# processing.net
KiCad netlist of a schematic drawn in EAGLE
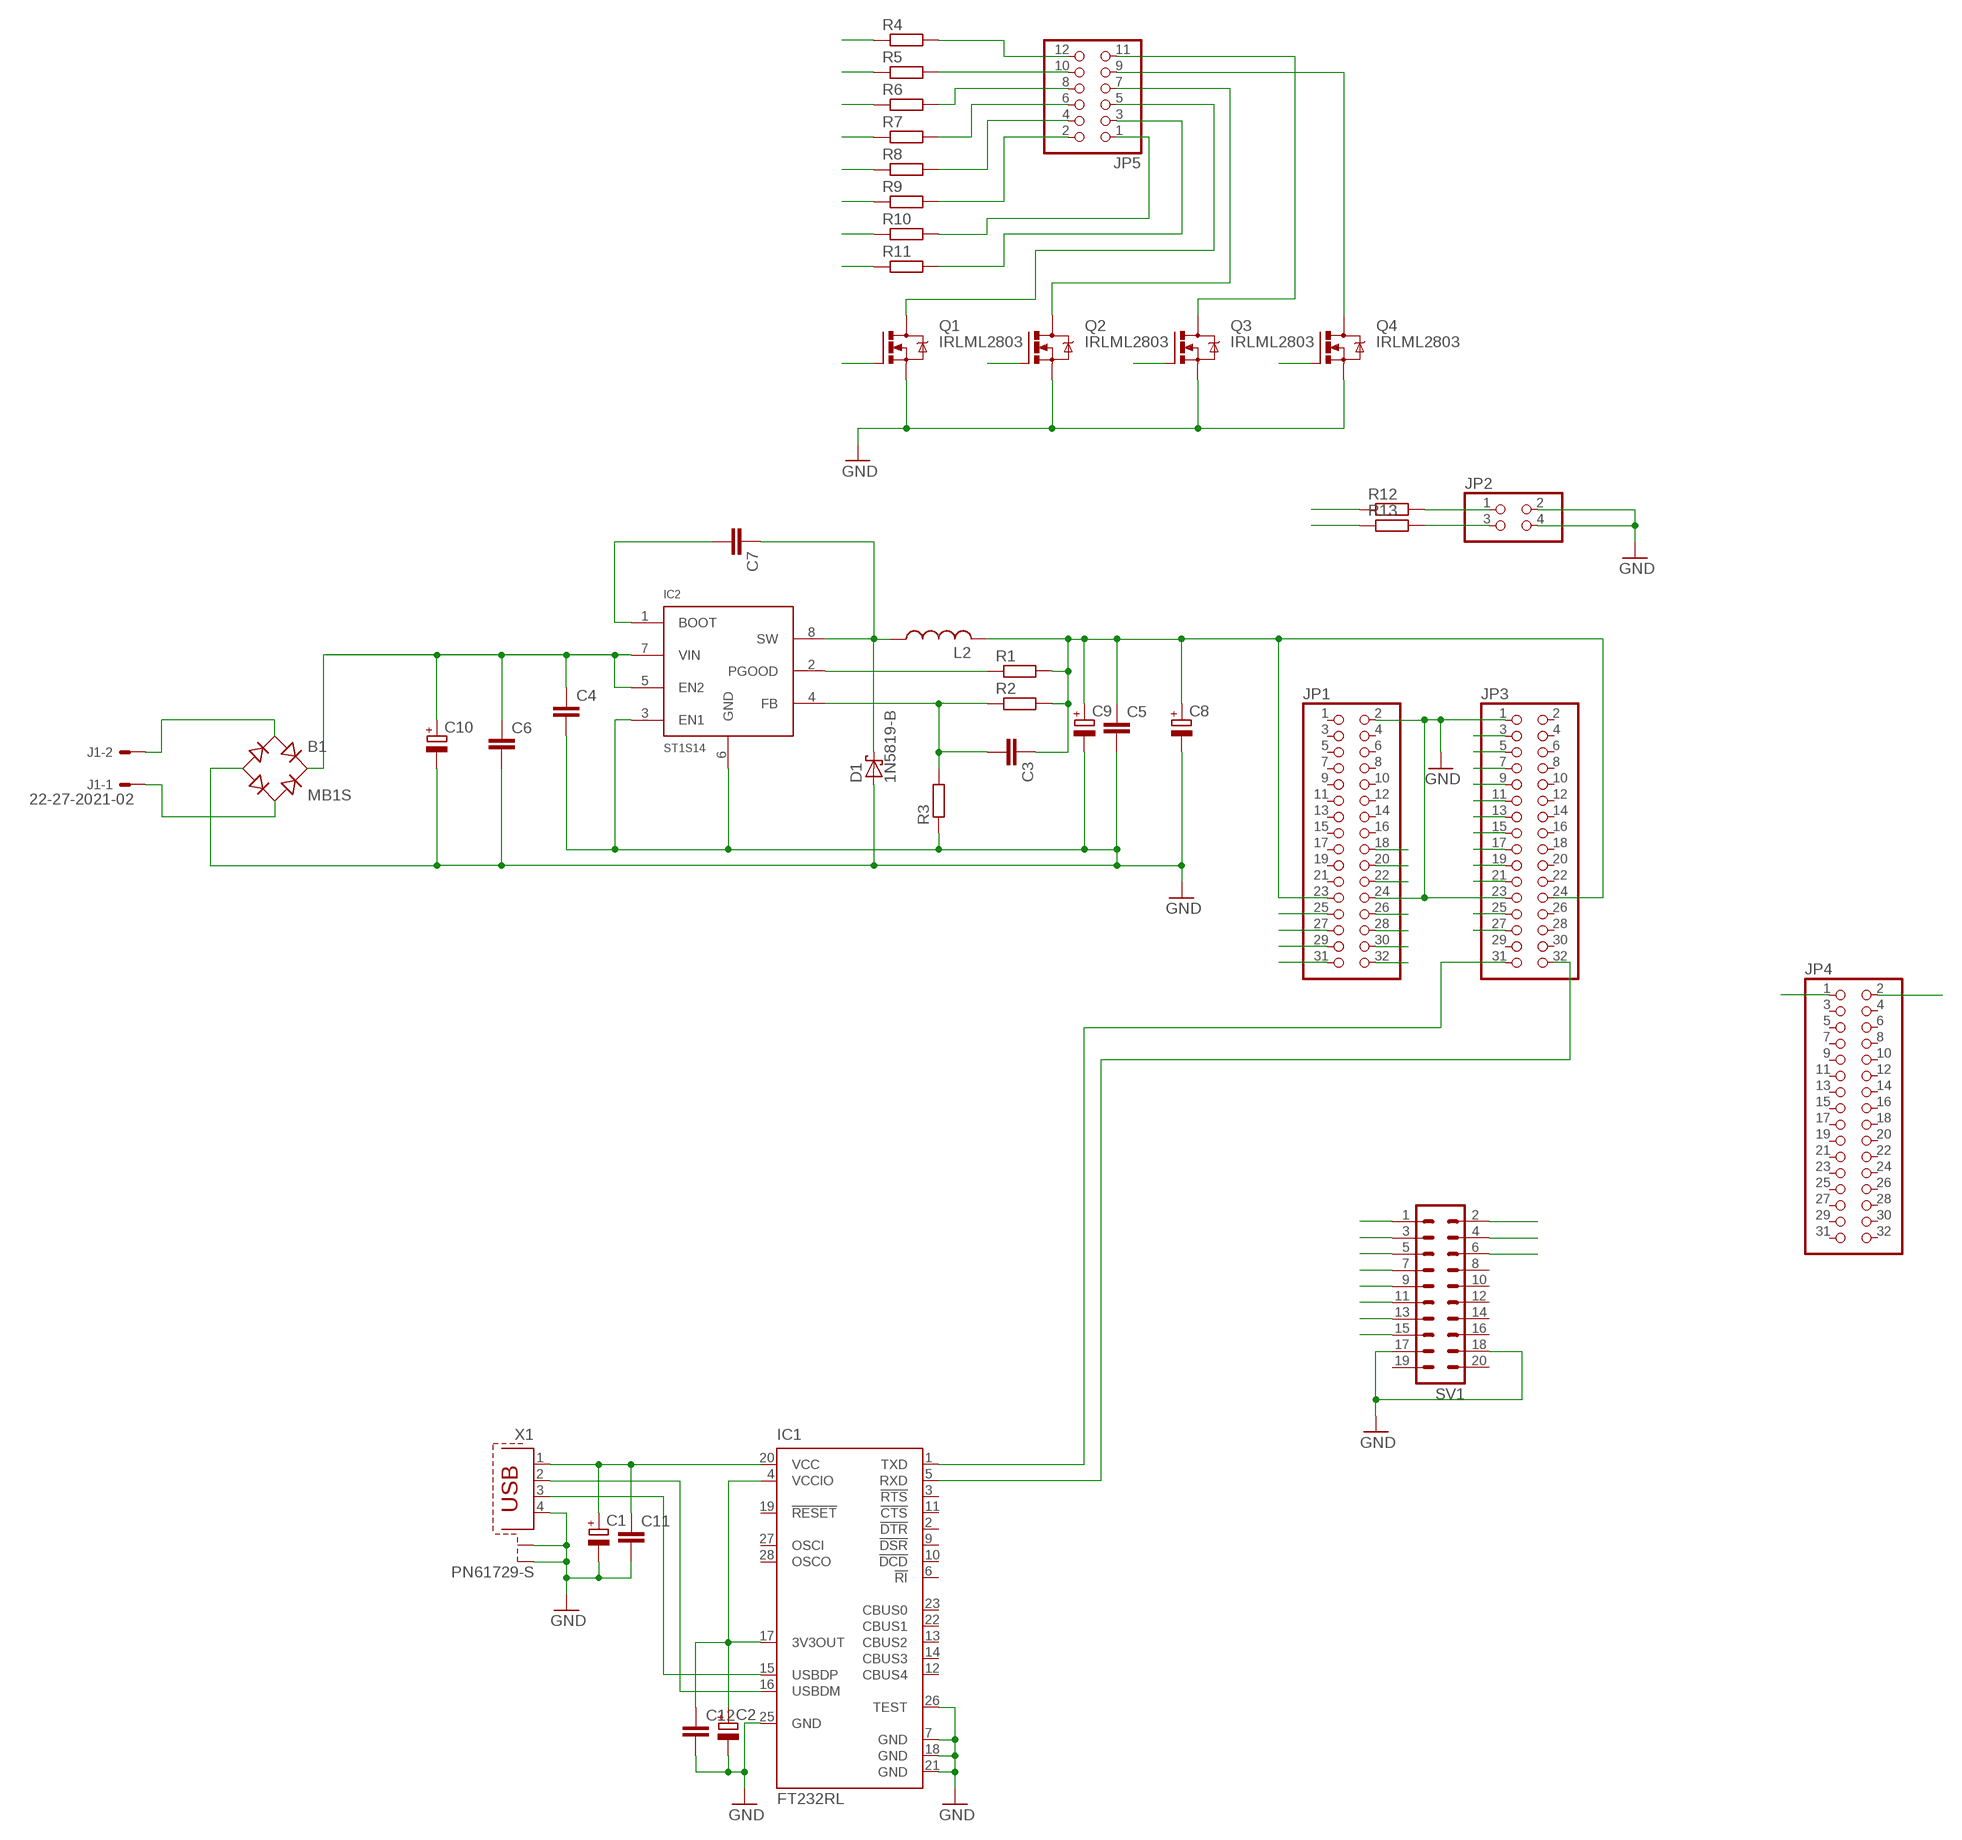
[diagram p0: schematic, sheet 1]

(export (version "E")
  (design (tool "Eeschema 10.0.6"))
  (components
    (comp (ref "B1")
      (value "MB1S")
      (footprint "eagle-import:SOIC-4")
      (libsource (lib "eagle-import") (part "MBS1"))
    )
    (comp (ref "C1")
      (value "CPOL-EUE2.5-5")
      (footprint "eagle-import:E2,5-5")
      (libsource (lib "eagle-import") (part "CPOL-EUE2.5-5"))
    )
    (comp (ref "C2")
      (value "CPOL-EUE2.5-5")
      (footprint "eagle-import:E2,5-5")
      (libsource (lib "eagle-import") (part "CPOL-EUE2.5-5"))
    )
    (comp (ref "C3")
      (value "C-EUC0805")
      (footprint "eagle-import:C0805")
      (libsource (lib "eagle-import") (part "C-EUC0805"))
    )
    (comp (ref "C4")
      (value "C-EUC0805")
      (footprint "eagle-import:C0805")
      (libsource (lib "eagle-import") (part "C-EUC0805"))
    )
    (comp (ref "C5")
      (value "C-EUC0805")
      (footprint "eagle-import:C0805")
      (libsource (lib "eagle-import") (part "C-EUC0805"))
    )
    (comp (ref "C6")
      (value "C-EUC0805")
      (footprint "eagle-import:C0805")
      (libsource (lib "eagle-import") (part "C-EUC0805"))
    )
    (comp (ref "C7")
      (value "C-EUC0805")
      (footprint "eagle-import:C0805")
      (libsource (lib "eagle-import") (part "C-EUC0805"))
    )
    (comp (ref "C8")
      (value "CPOL-EUE2.5-6")
      (footprint "eagle-import:E2,5-6")
      (libsource (lib "eagle-import") (part "CPOL-EUE2.5-6"))
    )
    (comp (ref "C9")
      (value "CPOL-EUSMCB")
      (footprint "eagle-import:SMC_B")
      (libsource (lib "eagle-import") (part "CPOL-EUSMCB"))
    )
    (comp (ref "C10")
      (value "CPOL-EUE2.5-7")
      (footprint "eagle-import:E2,5-7")
      (libsource (lib "eagle-import") (part "CPOL-EUE2.5-7"))
    )
    (comp (ref "C11")
      (value "C-EUC0603")
      (footprint "eagle-import:C0603")
      (libsource (lib "eagle-import") (part "C-EUC0603"))
    )
    (comp (ref "C12")
      (value "C-EUC0603")
      (footprint "eagle-import:C0603")
      (libsource (lib "eagle-import") (part "C-EUC0603"))
    )
    (comp (ref "D1")
      (value "1N5819-B")
      (footprint "eagle-import:DO41-7.6")
      (libsource (lib "eagle-import") (part "1N5819-B"))
    )
    (comp (ref "IC1")
      (value "FT232RL")
      (footprint "eagle-import:SSOP28")
      (libsource (lib "eagle-import") (part "FT232RL"))
    )
    (comp (ref "IC2")
      (value "ST1S14")
      (footprint "eagle-import:SO8")
      (libsource (lib "eagle-import") (part "ST1S14"))
    )
    (comp (ref "J1")
      (value "22-27-2021-02")
      (footprint "eagle-import:6410-02")
      (libsource (lib "eagle-import") (part "22-?-0227-2021"))
    )
    (comp (ref "JP1")
      (value "PINHD-2X16M")
      (footprint "eagle-import:2X16M")
      (libsource (lib "eagle-import") (part "PINHD-2X16M"))
    )
    (comp (ref "JP2")
      (value "PINHD-2X2")
      (footprint "eagle-import:2X02")
      (libsource (lib "eagle-import") (part "PINHD-2X2"))
    )
    (comp (ref "JP3")
      (value "PINHD-2X16M")
      (footprint "eagle-import:2X16M")
      (libsource (lib "eagle-import") (part "PINHD-2X16M"))
    )
    (comp (ref "JP4")
      (value "PINHD-2X16M")
      (footprint "eagle-import:2X16M")
      (libsource (lib "eagle-import") (part "PINHD-2X16M"))
    )
    (comp (ref "JP5")
      (value "PINHD-2X6")
      (footprint "eagle-import:2X06")
      (libsource (lib "eagle-import") (part "PINHD-2X6"))
    )
    (comp (ref "L2")
      (value "L-USWE-TPC")
      (footprint "eagle-import:POWER-CHOKE_WE-TPC")
      (libsource (lib "eagle-import") (part "L-USWE-TPC"))
    )
    (comp (ref "Q1")
      (value "IRLML2803")
      (footprint "eagle-import:SOT23")
      (libsource (lib "eagle-import") (part "IRLML2803"))
    )
    (comp (ref "Q2")
      (value "IRLML2803")
      (footprint "eagle-import:SOT23")
      (libsource (lib "eagle-import") (part "IRLML2803"))
    )
    (comp (ref "Q3")
      (value "IRLML2803")
      (footprint "eagle-import:SOT23")
      (libsource (lib "eagle-import") (part "IRLML2803"))
    )
    (comp (ref "Q4")
      (value "IRLML2803")
      (footprint "eagle-import:SOT23")
      (libsource (lib "eagle-import") (part "IRLML2803"))
    )
    (comp (ref "R1")
      (value "R-EU_R0805")
      (footprint "eagle-import:R0805")
      (libsource (lib "eagle-import") (part "R-EU_R0805"))
    )
    (comp (ref "R2")
      (value "R-EU_R0805")
      (footprint "eagle-import:R0805")
      (libsource (lib "eagle-import") (part "R-EU_R0805"))
    )
    (comp (ref "R3")
      (value "R-EU_R0805")
      (footprint "eagle-import:R0805")
      (libsource (lib "eagle-import") (part "R-EU_R0805"))
    )
    (comp (ref "R4")
      (value "R-EU_R0603")
      (footprint "eagle-import:R0603")
      (libsource (lib "eagle-import") (part "R-EU_R0603"))
    )
    (comp (ref "R5")
      (value "R-EU_R0603")
      (footprint "eagle-import:R0603")
      (libsource (lib "eagle-import") (part "R-EU_R0603"))
    )
    (comp (ref "R6")
      (value "R-EU_R0603")
      (footprint "eagle-import:R0603")
      (libsource (lib "eagle-import") (part "R-EU_R0603"))
    )
    (comp (ref "R7")
      (value "R-EU_R0603")
      (footprint "eagle-import:R0603")
      (libsource (lib "eagle-import") (part "R-EU_R0603"))
    )
    (comp (ref "R8")
      (value "R-EU_R0603")
      (footprint "eagle-import:R0603")
      (libsource (lib "eagle-import") (part "R-EU_R0603"))
    )
    (comp (ref "R9")
      (value "R-EU_R0603")
      (footprint "eagle-import:R0603")
      (libsource (lib "eagle-import") (part "R-EU_R0603"))
    )
    (comp (ref "R10")
      (value "R-EU_R0603")
      (footprint "eagle-import:R0603")
      (libsource (lib "eagle-import") (part "R-EU_R0603"))
    )
    (comp (ref "R11")
      (value "R-EU_R0603")
      (footprint "eagle-import:R0603")
      (libsource (lib "eagle-import") (part "R-EU_R0603"))
    )
    (comp (ref "R12")
      (value "R-EU_R0603")
      (footprint "eagle-import:R0603")
      (libsource (lib "eagle-import") (part "R-EU_R0603"))
    )
    (comp (ref "R13")
      (value "R-EU_R0603")
      (footprint "eagle-import:R0603")
      (libsource (lib "eagle-import") (part "R-EU_R0603"))
    )
    (comp (ref "SV1")
      (value "MA10-2W")
      (footprint "eagle-import:MA10-2W")
      (libsource (lib "eagle-import") (part "MA10-2W"))
    )
    (comp (ref "X1")
      (value "PN61729-S")
      (footprint "eagle-import:PN61729-S")
      (libsource (lib "eagle-import") (part "PN61729-S"))
    )
  )
  (nets
    (net (code "1") (name "/L1") (class "Default")
      (node (ref "JP3") (pin "17") (pinfunction "17_17") (pintype "passive"))
      (node (ref "R4") (pin "1") (pinfunction "1_1") (pintype "passive"))
    )
    (net (code "2") (name "/L2") (class "Default")
      (node (ref "JP3") (pin "15") (pinfunction "15_15") (pintype "passive"))
      (node (ref "R5") (pin "1") (pinfunction "1_1") (pintype "passive"))
    )
    (net (code "3") (name "/L3") (class "Default")
      (node (ref "JP3") (pin "13") (pinfunction "13_13") (pintype "passive"))
      (node (ref "R6") (pin "1") (pinfunction "1_1") (pintype "passive"))
    )
    (net (code "4") (name "/L4") (class "Default")
      (node (ref "JP3") (pin "11") (pinfunction "11_11") (pintype "passive"))
      (node (ref "R7") (pin "1") (pinfunction "1_1") (pintype "passive"))
    )
    (net (code "5") (name "/L5") (class "Default")
      (node (ref "JP3") (pin "9") (pinfunction "9_9") (pintype "passive"))
      (node (ref "R8") (pin "1") (pinfunction "1_1") (pintype "passive"))
    )
    (net (code "6") (name "/L6") (class "Default")
      (node (ref "JP3") (pin "7") (pinfunction "7_7") (pintype "passive"))
      (node (ref "R9") (pin "1") (pinfunction "1_1") (pintype "passive"))
    )
    (net (code "7") (name "/L7") (class "Default")
      (node (ref "JP3") (pin "5") (pinfunction "5_5") (pintype "passive"))
      (node (ref "R10") (pin "1") (pinfunction "1_1") (pintype "passive"))
    )
    (net (code "8") (name "/L8") (class "Default")
      (node (ref "JP3") (pin "3") (pinfunction "3_3") (pintype "passive"))
      (node (ref "R11") (pin "1") (pinfunction "1_1") (pintype "passive"))
    )
    (net (code "9") (name "/LED1") (class "Default")
      (node (ref "JP4") (pin "1") (pinfunction "1_1") (pintype "passive"))
      (node (ref "R12") (pin "1") (pinfunction "1_1") (pintype "passive"))
    )
    (net (code "10") (name "/LED2") (class "Default")
      (node (ref "JP4") (pin "2") (pinfunction "2_2") (pintype "passive"))
      (node (ref "R13") (pin "1") (pinfunction "1_1") (pintype "passive"))
    )
    (net (code "11") (name "/Q1") (class "Default")
      (node (ref "JP3") (pin "27") (pinfunction "27_27") (pintype "passive"))
      (node (ref "Q1") (pin "1") (pinfunction "G_1") (pintype "passive"))
    )
    (net (code "12") (name "/Q2") (class "Default")
      (node (ref "JP3") (pin "25") (pinfunction "25_25") (pintype "passive"))
      (node (ref "Q2") (pin "1") (pinfunction "G_1") (pintype "passive"))
    )
    (net (code "13") (name "/Q3") (class "Default")
      (node (ref "JP3") (pin "19") (pinfunction "19_19") (pintype "passive"))
      (node (ref "Q3") (pin "1") (pinfunction "G_1") (pintype "passive"))
    )
    (net (code "14") (name "/Q4") (class "Default")
      (node (ref "JP3") (pin "21") (pinfunction "21_21") (pintype "passive"))
      (node (ref "Q4") (pin "1") (pinfunction "G_1") (pintype "passive"))
    )
    (net (code "15") (name "/R1") (class "Default")
      (node (ref "JP1") (pin "18") (pinfunction "18_18") (pintype "passive"))
      (node (ref "SV1") (pin "6") (pinfunction "6_6") (pintype "passive"))
    )
    (net (code "16") (name "/R2") (class "Default")
      (node (ref "JP1") (pin "20") (pinfunction "20_20") (pintype "passive"))
      (node (ref "SV1") (pin "4") (pinfunction "4_4") (pintype "passive"))
    )
    (net (code "17") (name "/R3") (class "Default")
      (node (ref "JP1") (pin "22") (pinfunction "22_22") (pintype "passive"))
      (node (ref "SV1") (pin "2") (pinfunction "2_2") (pintype "passive"))
    )
    (net (code "18") (name "/R4") (class "Default")
      (node (ref "JP1") (pin "26") (pinfunction "26_26") (pintype "passive"))
      (node (ref "SV1") (pin "1") (pinfunction "1_1") (pintype "passive"))
    )
    (net (code "19") (name "/R5") (class "Default")
      (node (ref "JP1") (pin "28") (pinfunction "28_28") (pintype "passive"))
      (node (ref "SV1") (pin "3") (pinfunction "3_3") (pintype "passive"))
    )
    (net (code "20") (name "/R6") (class "Default")
      (node (ref "JP1") (pin "30") (pinfunction "30_30") (pintype "passive"))
      (node (ref "SV1") (pin "5") (pinfunction "5_5") (pintype "passive"))
    )
    (net (code "21") (name "/R7") (class "Default")
      (node (ref "JP1") (pin "32") (pinfunction "32_32") (pintype "passive"))
      (node (ref "SV1") (pin "7") (pinfunction "7_7") (pintype "passive"))
    )
    (net (code "22") (name "/R8") (class "Default")
      (node (ref "JP1") (pin "31") (pinfunction "31_31") (pintype "passive"))
      (node (ref "SV1") (pin "9") (pinfunction "9_9") (pintype "passive"))
    )
    (net (code "23") (name "/R9") (class "Default")
      (node (ref "JP1") (pin "29") (pinfunction "29_29") (pintype "passive"))
      (node (ref "SV1") (pin "11") (pinfunction "11_11") (pintype "passive"))
    )
    (net (code "24") (name "/R10") (class "Default")
      (node (ref "JP1") (pin "27") (pinfunction "27_27") (pintype "passive"))
      (node (ref "SV1") (pin "13") (pinfunction "13_13") (pintype "passive"))
    )
    (net (code "25") (name "/R11") (class "Default")
      (node (ref "JP1") (pin "25") (pinfunction "25_25") (pintype "passive"))
      (node (ref "SV1") (pin "15") (pinfunction "15_15") (pintype "passive"))
    )
    (net (code "26") (name "GND") (class "Default")
      (node (ref "B1") (pin "-") (pinfunction "-_-") (pintype "passive"))
      (node (ref "C1") (pin "-") (pinfunction "-_-") (pintype "passive"))
      (node (ref "C10") (pin "-") (pinfunction "-_-") (pintype "passive"))
      (node (ref "C11") (pin "2") (pinfunction "2_2") (pintype "passive"))
      (node (ref "C12") (pin "2") (pinfunction "2_2") (pintype "passive"))
      (node (ref "C2") (pin "-") (pinfunction "-_-") (pintype "passive"))
      (node (ref "C4") (pin "2") (pinfunction "2_2") (pintype "passive"))
      (node (ref "C5") (pin "2") (pinfunction "2_2") (pintype "passive"))
      (node (ref "C6") (pin "2") (pinfunction "2_2") (pintype "passive"))
      (node (ref "C8") (pin "-") (pinfunction "-_-") (pintype "passive"))
      (node (ref "C9") (pin "-") (pinfunction "-_-") (pintype "passive"))
      (node (ref "D1") (pin "A") (pinfunction "A_A") (pintype "passive"))
      (node (ref "IC1") (pin "18") (pinfunction "GND_18") (pintype "power_in"))
      (node (ref "IC1") (pin "21") (pinfunction "GND_21") (pintype "power_in"))
      (node (ref "IC1") (pin "25") (pinfunction "GND_25") (pintype "power_in"))
      (node (ref "IC1") (pin "26") (pinfunction "TEST_26") (pintype "input"))
      (node (ref "IC1") (pin "7") (pinfunction "GND_7") (pintype "power_in"))
      (node (ref "IC2") (pin "3") (pinfunction "EN1_3") (pintype "bidirectional"))
      (node (ref "IC2") (pin "6") (pinfunction "GND_6") (pintype "bidirectional"))
      (node (ref "JP1") (pin "2") (pinfunction "2_2") (pintype "passive"))
      (node (ref "JP1") (pin "24") (pinfunction "24_24") (pintype "passive"))
      (node (ref "JP2") (pin "2") (pinfunction "2_2") (pintype "passive"))
      (node (ref "JP2") (pin "4") (pinfunction "4_4") (pintype "passive"))
      (node (ref "JP3") (pin "1") (pinfunction "1_1") (pintype "passive"))
      (node (ref "JP3") (pin "23") (pinfunction "23_23") (pintype "passive"))
      (node (ref "Q1") (pin "2") (pinfunction "S_2") (pintype "passive"))
      (node (ref "Q2") (pin "2") (pinfunction "S_2") (pintype "passive"))
      (node (ref "Q3") (pin "2") (pinfunction "S_2") (pintype "passive"))
      (node (ref "Q4") (pin "2") (pinfunction "S_2") (pintype "passive"))
      (node (ref "R3") (pin "1") (pinfunction "1_1") (pintype "passive"))
      (node (ref "SV1") (pin "17") (pinfunction "17_17") (pintype "passive"))
      (node (ref "SV1") (pin "18") (pinfunction "18_18") (pintype "passive"))
      (node (ref "X1") (pin "4") (pinfunction "4_4") (pintype "passive"))
      (node (ref "X1") (pin "S1") (pinfunction "S1_S1") (pintype "passive"))
      (node (ref "X1") (pin "S2") (pinfunction "S2_S2") (pintype "passive"))
    )
    (net (code "27") (name "Net-(B1-AC1)") (class "Default")
      (node (ref "B1") (pin "~1") (pinfunction "AC1_~1") (pintype "passive"))
      (node (ref "J1") (pin "2") (pinfunction "S_2") (pintype "passive"))
    )
    (net (code "28") (name "Net-(B1-AC2)") (class "Default")
      (node (ref "B1") (pin "~2") (pinfunction "AC2_~2") (pintype "passive"))
      (node (ref "J1") (pin "1") (pinfunction "S_1") (pintype "passive"))
    )
    (net (code "29") (name "Net-(C3-Pad1)") (class "Default")
      (node (ref "C3") (pin "1") (pinfunction "1_1") (pintype "passive"))
      (node (ref "C5") (pin "1") (pinfunction "1_1") (pintype "passive"))
      (node (ref "C8") (pin "+") (pinfunction "+_+") (pintype "passive"))
      (node (ref "C9") (pin "+") (pinfunction "+_+") (pintype "passive"))
      (node (ref "JP1") (pin "23") (pinfunction "23_23") (pintype "passive"))
      (node (ref "JP3") (pin "24") (pinfunction "24_24") (pintype "passive"))
      (node (ref "L2") (pin "2") (pinfunction "2_2") (pintype "passive"))
      (node (ref "R1") (pin "2") (pinfunction "2_2") (pintype "passive"))
      (node (ref "R2") (pin "2") (pinfunction "2_2") (pintype "passive"))
    )
    (net (code "30") (name "Net-(IC1-3V3OUT)") (class "Default")
      (node (ref "C12") (pin "1") (pinfunction "1_1") (pintype "passive"))
      (node (ref "C2") (pin "+") (pinfunction "+_+") (pintype "passive"))
      (node (ref "IC1") (pin "17") (pinfunction "3V3OUT_17") (pintype "output"))
      (node (ref "IC1") (pin "4") (pinfunction "VCCIO_4") (pintype "power_in"))
    )
    (net (code "31") (name "Net-(IC1-RXD)") (class "Default")
      (node (ref "IC1") (pin "5") (pinfunction "RXD_5") (pintype "input"))
      (node (ref "JP3") (pin "32") (pinfunction "32_32") (pintype "passive"))
    )
    (net (code "32") (name "Net-(IC1-TXD)") (class "Default")
      (node (ref "IC1") (pin "1") (pinfunction "TXD_1") (pintype "output"))
      (node (ref "JP3") (pin "31") (pinfunction "31_31") (pintype "passive"))
    )
    (net (code "33") (name "Net-(IC1-USBDM)") (class "Default")
      (node (ref "IC1") (pin "16") (pinfunction "USBDM_16") (pintype "bidirectional"))
      (node (ref "X1") (pin "2") (pinfunction "2_2") (pintype "passive"))
    )
    (net (code "34") (name "Net-(IC1-USBDP)") (class "Default")
      (node (ref "IC1") (pin "15") (pinfunction "USBDP_15") (pintype "bidirectional"))
      (node (ref "X1") (pin "3") (pinfunction "3_3") (pintype "passive"))
    )
    (net (code "35") (name "Net-(IC1-VCC)") (class "Default")
      (node (ref "C1") (pin "+") (pinfunction "+_+") (pintype "passive"))
      (node (ref "C11") (pin "1") (pinfunction "1_1") (pintype "passive"))
      (node (ref "IC1") (pin "20") (pinfunction "VCC_20") (pintype "power_in"))
      (node (ref "X1") (pin "1") (pinfunction "1_1") (pintype "passive"))
    )
    (net (code "36") (name "Net-(IC2-BOOT)") (class "Default")
      (node (ref "C7") (pin "2") (pinfunction "2_2") (pintype "passive"))
      (node (ref "IC2") (pin "1") (pinfunction "BOOT_1") (pintype "bidirectional"))
    )
    (net (code "37") (name "Net-(IC2-EN2)") (class "Default")
      (node (ref "B1") (pin "+") (pinfunction "+_+") (pintype "passive"))
      (node (ref "C10") (pin "+") (pinfunction "+_+") (pintype "passive"))
      (node (ref "C4") (pin "1") (pinfunction "1_1") (pintype "passive"))
      (node (ref "C6") (pin "1") (pinfunction "1_1") (pintype "passive"))
      (node (ref "IC2") (pin "5") (pinfunction "EN2_5") (pintype "bidirectional"))
      (node (ref "IC2") (pin "7") (pinfunction "VIN_7") (pintype "bidirectional"))
    )
    (net (code "38") (name "Net-(IC2-FB)") (class "Default")
      (node (ref "C3") (pin "2") (pinfunction "2_2") (pintype "passive"))
      (node (ref "IC2") (pin "4") (pinfunction "FB_4") (pintype "bidirectional"))
      (node (ref "R2") (pin "1") (pinfunction "1_1") (pintype "passive"))
      (node (ref "R3") (pin "2") (pinfunction "2_2") (pintype "passive"))
    )
    (net (code "39") (name "Net-(IC2-PGOOD)") (class "Default")
      (node (ref "IC2") (pin "2") (pinfunction "PGOOD_2") (pintype "bidirectional"))
      (node (ref "R1") (pin "1") (pinfunction "1_1") (pintype "passive"))
    )
    (net (code "40") (name "Net-(IC2-SW)") (class "Default")
      (node (ref "C7") (pin "1") (pinfunction "1_1") (pintype "passive"))
      (node (ref "D1") (pin "C") (pinfunction "C_C") (pintype "passive"))
      (node (ref "IC2") (pin "8") (pinfunction "SW_8") (pintype "bidirectional"))
      (node (ref "L2") (pin "1") (pinfunction "1_1") (pintype "passive"))
    )
    (net (code "41") (name "Net-(JP2-Pad1)") (class "Default")
      (node (ref "JP2") (pin "1") (pinfunction "1_1") (pintype "passive"))
      (node (ref "R12") (pin "2") (pinfunction "2_2") (pintype "passive"))
    )
    (net (code "42") (name "Net-(JP2-Pad3)") (class "Default")
      (node (ref "JP2") (pin "3") (pinfunction "3_3") (pintype "passive"))
      (node (ref "R13") (pin "2") (pinfunction "2_2") (pintype "passive"))
    )
    (net (code "43") (name "Net-(JP5-Pad1)") (class "Default")
      (node (ref "JP5") (pin "1") (pinfunction "1_1") (pintype "passive"))
      (node (ref "R10") (pin "2") (pinfunction "2_2") (pintype "passive"))
    )
    (net (code "44") (name "Net-(JP5-Pad2)") (class "Default")
      (node (ref "JP5") (pin "2") (pinfunction "2_2") (pintype "passive"))
      (node (ref "R9") (pin "2") (pinfunction "2_2") (pintype "passive"))
    )
    (net (code "45") (name "Net-(JP5-Pad3)") (class "Default")
      (node (ref "JP5") (pin "3") (pinfunction "3_3") (pintype "passive"))
      (node (ref "R11") (pin "2") (pinfunction "2_2") (pintype "passive"))
    )
    (net (code "46") (name "Net-(JP5-Pad4)") (class "Default")
      (node (ref "JP5") (pin "4") (pinfunction "4_4") (pintype "passive"))
      (node (ref "R8") (pin "2") (pinfunction "2_2") (pintype "passive"))
    )
    (net (code "47") (name "Net-(JP5-Pad6)") (class "Default")
      (node (ref "JP5") (pin "6") (pinfunction "6_6") (pintype "passive"))
      (node (ref "R7") (pin "2") (pinfunction "2_2") (pintype "passive"))
    )
    (net (code "48") (name "Net-(JP5-Pad8)") (class "Default")
      (node (ref "JP5") (pin "8") (pinfunction "8_8") (pintype "passive"))
      (node (ref "R6") (pin "2") (pinfunction "2_2") (pintype "passive"))
    )
    (net (code "49") (name "Net-(JP5-Pad10)") (class "Default")
      (node (ref "JP5") (pin "10") (pinfunction "10_10") (pintype "passive"))
      (node (ref "R5") (pin "2") (pinfunction "2_2") (pintype "passive"))
    )
    (net (code "50") (name "Net-(JP5-Pad12)") (class "Default")
      (node (ref "JP5") (pin "12") (pinfunction "12_12") (pintype "passive"))
      (node (ref "R4") (pin "2") (pinfunction "2_2") (pintype "passive"))
    )
    (net (code "51") (name "Net-(Q1-D)") (class "Default")
      (node (ref "JP5") (pin "5") (pinfunction "5_5") (pintype "passive"))
      (node (ref "Q1") (pin "3") (pinfunction "D_3") (pintype "passive"))
    )
    (net (code "52") (name "Net-(Q2-D)") (class "Default")
      (node (ref "JP5") (pin "7") (pinfunction "7_7") (pintype "passive"))
      (node (ref "Q2") (pin "3") (pinfunction "D_3") (pintype "passive"))
    )
    (net (code "53") (name "Net-(Q3-D)") (class "Default")
      (node (ref "JP5") (pin "11") (pinfunction "11_11") (pintype "passive"))
      (node (ref "Q3") (pin "3") (pinfunction "D_3") (pintype "passive"))
    )
    (net (code "54") (name "Net-(Q4-D)") (class "Default")
      (node (ref "JP5") (pin "9") (pinfunction "9_9") (pintype "passive"))
      (node (ref "Q4") (pin "3") (pinfunction "D_3") (pintype "passive"))
    )
    (net (code "55") (name "unconnected-(IC1-CBUS0-Pad23)") (class "Default")
      (node (ref "IC1") (pin "23") (pinfunction "CBUS0_23") (pintype "bidirectional"))
    )
    (net (code "56") (name "unconnected-(IC1-CBUS1-Pad22)") (class "Default")
      (node (ref "IC1") (pin "22") (pinfunction "CBUS1_22") (pintype "bidirectional"))
    )
    (net (code "57") (name "unconnected-(IC1-CBUS2-Pad13)") (class "Default")
      (node (ref "IC1") (pin "13") (pinfunction "CBUS2_13") (pintype "bidirectional"))
    )
    (net (code "58") (name "unconnected-(IC1-CBUS3-Pad14)") (class "Default")
      (node (ref "IC1") (pin "14") (pinfunction "CBUS3_14") (pintype "bidirectional"))
    )
    (net (code "59") (name "unconnected-(IC1-CBUS4-Pad12)") (class "Default")
      (node (ref "IC1") (pin "12") (pinfunction "CBUS4_12") (pintype "bidirectional"))
    )
    (net (code "60") (name "unconnected-(IC1-OSCI-Pad27)") (class "Default")
      (node (ref "IC1") (pin "27") (pinfunction "OSCI_27") (pintype "input"))
    )
    (net (code "61") (name "unconnected-(IC1-OSCO-Pad28)") (class "Default")
      (node (ref "IC1") (pin "28") (pinfunction "OSCO_28") (pintype "output"))
    )
    (net (code "62") (name "unconnected-(IC1-~{CTS}-Pad11)") (class "Default")
      (node (ref "IC1") (pin "11") (pinfunction "~{CTS}_11") (pintype "input"))
    )
    (net (code "63") (name "unconnected-(IC1-~{DCD}-Pad10)") (class "Default")
      (node (ref "IC1") (pin "10") (pinfunction "~{DCD}_10") (pintype "input"))
    )
    (net (code "64") (name "unconnected-(IC1-~{DSR}-Pad9)") (class "Default")
      (node (ref "IC1") (pin "9") (pinfunction "~{DSR}_9") (pintype "input"))
    )
    (net (code "65") (name "unconnected-(IC1-~{DTR}-Pad2)") (class "Default")
      (node (ref "IC1") (pin "2") (pinfunction "~{DTR}_2") (pintype "output"))
    )
    (net (code "66") (name "unconnected-(IC1-~{RESET}-Pad19)") (class "Default")
      (node (ref "IC1") (pin "19") (pinfunction "~{RESET}_19") (pintype "input"))
    )
    (net (code "67") (name "unconnected-(IC1-~{RI}-Pad6)") (class "Default")
      (node (ref "IC1") (pin "6") (pinfunction "~{RI}_6") (pintype "input"))
    )
    (net (code "68") (name "unconnected-(IC1-~{RTS}-Pad3)") (class "Default")
      (node (ref "IC1") (pin "3") (pinfunction "~{RTS}_3") (pintype "output"))
    )
    (net (code "69") (name "unconnected-(JP1-Pad1)") (class "Default")
      (node (ref "JP1") (pin "1") (pinfunction "1_1") (pintype "passive"))
    )
    (net (code "70") (name "unconnected-(JP1-Pad3)") (class "Default")
      (node (ref "JP1") (pin "3") (pinfunction "3_3") (pintype "passive"))
    )
    (net (code "71") (name "unconnected-(JP1-Pad4)") (class "Default")
      (node (ref "JP1") (pin "4") (pinfunction "4_4") (pintype "passive"))
    )
    (net (code "72") (name "unconnected-(JP1-Pad5)") (class "Default")
      (node (ref "JP1") (pin "5") (pinfunction "5_5") (pintype "passive"))
    )
    (net (code "73") (name "unconnected-(JP1-Pad6)") (class "Default")
      (node (ref "JP1") (pin "6") (pinfunction "6_6") (pintype "passive"))
    )
    (net (code "74") (name "unconnected-(JP1-Pad7)") (class "Default")
      (node (ref "JP1") (pin "7") (pinfunction "7_7") (pintype "passive"))
    )
    (net (code "75") (name "unconnected-(JP1-Pad8)") (class "Default")
      (node (ref "JP1") (pin "8") (pinfunction "8_8") (pintype "passive"))
    )
    (net (code "76") (name "unconnected-(JP1-Pad9)") (class "Default")
      (node (ref "JP1") (pin "9") (pinfunction "9_9") (pintype "passive"))
    )
    (net (code "77") (name "unconnected-(JP1-Pad10)") (class "Default")
      (node (ref "JP1") (pin "10") (pinfunction "10_10") (pintype "passive"))
    )
    (net (code "78") (name "unconnected-(JP1-Pad11)") (class "Default")
      (node (ref "JP1") (pin "11") (pinfunction "11_11") (pintype "passive"))
    )
    (net (code "79") (name "unconnected-(JP1-Pad12)") (class "Default")
      (node (ref "JP1") (pin "12") (pinfunction "12_12") (pintype "passive"))
    )
    (net (code "80") (name "unconnected-(JP1-Pad13)") (class "Default")
      (node (ref "JP1") (pin "13") (pinfunction "13_13") (pintype "passive"))
    )
    (net (code "81") (name "unconnected-(JP1-Pad14)") (class "Default")
      (node (ref "JP1") (pin "14") (pinfunction "14_14") (pintype "passive"))
    )
    (net (code "82") (name "unconnected-(JP1-Pad15)") (class "Default")
      (node (ref "JP1") (pin "15") (pinfunction "15_15") (pintype "passive"))
    )
    (net (code "83") (name "unconnected-(JP1-Pad16)") (class "Default")
      (node (ref "JP1") (pin "16") (pinfunction "16_16") (pintype "passive"))
    )
    (net (code "84") (name "unconnected-(JP1-Pad17)") (class "Default")
      (node (ref "JP1") (pin "17") (pinfunction "17_17") (pintype "passive"))
    )
    (net (code "85") (name "unconnected-(JP1-Pad19)") (class "Default")
      (node (ref "JP1") (pin "19") (pinfunction "19_19") (pintype "passive"))
    )
    (net (code "86") (name "unconnected-(JP1-Pad21)") (class "Default")
      (node (ref "JP1") (pin "21") (pinfunction "21_21") (pintype "passive"))
    )
    (net (code "87") (name "unconnected-(JP3-Pad2)") (class "Default")
      (node (ref "JP3") (pin "2") (pinfunction "2_2") (pintype "passive"))
    )
    (net (code "88") (name "unconnected-(JP3-Pad4)") (class "Default")
      (node (ref "JP3") (pin "4") (pinfunction "4_4") (pintype "passive"))
    )
    (net (code "89") (name "unconnected-(JP3-Pad6)") (class "Default")
      (node (ref "JP3") (pin "6") (pinfunction "6_6") (pintype "passive"))
    )
    (net (code "90") (name "unconnected-(JP3-Pad8)") (class "Default")
      (node (ref "JP3") (pin "8") (pinfunction "8_8") (pintype "passive"))
    )
    (net (code "91") (name "unconnected-(JP3-Pad10)") (class "Default")
      (node (ref "JP3") (pin "10") (pinfunction "10_10") (pintype "passive"))
    )
    (net (code "92") (name "unconnected-(JP3-Pad12)") (class "Default")
      (node (ref "JP3") (pin "12") (pinfunction "12_12") (pintype "passive"))
    )
    (net (code "93") (name "unconnected-(JP3-Pad14)") (class "Default")
      (node (ref "JP3") (pin "14") (pinfunction "14_14") (pintype "passive"))
    )
    (net (code "94") (name "unconnected-(JP3-Pad16)") (class "Default")
      (node (ref "JP3") (pin "16") (pinfunction "16_16") (pintype "passive"))
    )
    (net (code "95") (name "unconnected-(JP3-Pad18)") (class "Default")
      (node (ref "JP3") (pin "18") (pinfunction "18_18") (pintype "passive"))
    )
    (net (code "96") (name "unconnected-(JP3-Pad20)") (class "Default")
      (node (ref "JP3") (pin "20") (pinfunction "20_20") (pintype "passive"))
    )
    (net (code "97") (name "unconnected-(JP3-Pad22)") (class "Default")
      (node (ref "JP3") (pin "22") (pinfunction "22_22") (pintype "passive"))
    )
    (net (code "98") (name "unconnected-(JP3-Pad26)") (class "Default")
      (node (ref "JP3") (pin "26") (pinfunction "26_26") (pintype "passive"))
    )
    (net (code "99") (name "unconnected-(JP3-Pad28)") (class "Default")
      (node (ref "JP3") (pin "28") (pinfunction "28_28") (pintype "passive"))
    )
    (net (code "100") (name "unconnected-(JP3-Pad29)") (class "Default")
      (node (ref "JP3") (pin "29") (pinfunction "29_29") (pintype "passive"))
    )
    (net (code "101") (name "unconnected-(JP3-Pad30)") (class "Default")
      (node (ref "JP3") (pin "30") (pinfunction "30_30") (pintype "passive"))
    )
    (net (code "102") (name "unconnected-(JP4-Pad3)") (class "Default")
      (node (ref "JP4") (pin "3") (pinfunction "3_3") (pintype "passive"))
    )
    (net (code "103") (name "unconnected-(JP4-Pad4)") (class "Default")
      (node (ref "JP4") (pin "4") (pinfunction "4_4") (pintype "passive"))
    )
    (net (code "104") (name "unconnected-(JP4-Pad5)") (class "Default")
      (node (ref "JP4") (pin "5") (pinfunction "5_5") (pintype "passive"))
    )
    (net (code "105") (name "unconnected-(JP4-Pad6)") (class "Default")
      (node (ref "JP4") (pin "6") (pinfunction "6_6") (pintype "passive"))
    )
    (net (code "106") (name "unconnected-(JP4-Pad7)") (class "Default")
      (node (ref "JP4") (pin "7") (pinfunction "7_7") (pintype "passive"))
    )
    (net (code "107") (name "unconnected-(JP4-Pad8)") (class "Default")
      (node (ref "JP4") (pin "8") (pinfunction "8_8") (pintype "passive"))
    )
    (net (code "108") (name "unconnected-(JP4-Pad9)") (class "Default")
      (node (ref "JP4") (pin "9") (pinfunction "9_9") (pintype "passive"))
    )
    (net (code "109") (name "unconnected-(JP4-Pad10)") (class "Default")
      (node (ref "JP4") (pin "10") (pinfunction "10_10") (pintype "passive"))
    )
    (net (code "110") (name "unconnected-(JP4-Pad11)") (class "Default")
      (node (ref "JP4") (pin "11") (pinfunction "11_11") (pintype "passive"))
    )
    (net (code "111") (name "unconnected-(JP4-Pad12)") (class "Default")
      (node (ref "JP4") (pin "12") (pinfunction "12_12") (pintype "passive"))
    )
    (net (code "112") (name "unconnected-(JP4-Pad13)") (class "Default")
      (node (ref "JP4") (pin "13") (pinfunction "13_13") (pintype "passive"))
    )
    (net (code "113") (name "unconnected-(JP4-Pad14)") (class "Default")
      (node (ref "JP4") (pin "14") (pinfunction "14_14") (pintype "passive"))
    )
    (net (code "114") (name "unconnected-(JP4-Pad15)") (class "Default")
      (node (ref "JP4") (pin "15") (pinfunction "15_15") (pintype "passive"))
    )
    (net (code "115") (name "unconnected-(JP4-Pad16)") (class "Default")
      (node (ref "JP4") (pin "16") (pinfunction "16_16") (pintype "passive"))
    )
    (net (code "116") (name "unconnected-(JP4-Pad17)") (class "Default")
      (node (ref "JP4") (pin "17") (pinfunction "17_17") (pintype "passive"))
    )
    (net (code "117") (name "unconnected-(JP4-Pad18)") (class "Default")
      (node (ref "JP4") (pin "18") (pinfunction "18_18") (pintype "passive"))
    )
    (net (code "118") (name "unconnected-(JP4-Pad19)") (class "Default")
      (node (ref "JP4") (pin "19") (pinfunction "19_19") (pintype "passive"))
    )
    (net (code "119") (name "unconnected-(JP4-Pad20)") (class "Default")
      (node (ref "JP4") (pin "20") (pinfunction "20_20") (pintype "passive"))
    )
    (net (code "120") (name "unconnected-(JP4-Pad21)") (class "Default")
      (node (ref "JP4") (pin "21") (pinfunction "21_21") (pintype "passive"))
    )
    (net (code "121") (name "unconnected-(JP4-Pad22)") (class "Default")
      (node (ref "JP4") (pin "22") (pinfunction "22_22") (pintype "passive"))
    )
    (net (code "122") (name "unconnected-(JP4-Pad23)") (class "Default")
      (node (ref "JP4") (pin "23") (pinfunction "23_23") (pintype "passive"))
    )
    (net (code "123") (name "unconnected-(JP4-Pad24)") (class "Default")
      (node (ref "JP4") (pin "24") (pinfunction "24_24") (pintype "passive"))
    )
    (net (code "124") (name "unconnected-(JP4-Pad25)") (class "Default")
      (node (ref "JP4") (pin "25") (pinfunction "25_25") (pintype "passive"))
    )
    (net (code "125") (name "unconnected-(JP4-Pad26)") (class "Default")
      (node (ref "JP4") (pin "26") (pinfunction "26_26") (pintype "passive"))
    )
    (net (code "126") (name "unconnected-(JP4-Pad27)") (class "Default")
      (node (ref "JP4") (pin "27") (pinfunction "27_27") (pintype "passive"))
    )
    (net (code "127") (name "unconnected-(JP4-Pad28)") (class "Default")
      (node (ref "JP4") (pin "28") (pinfunction "28_28") (pintype "passive"))
    )
    (net (code "128") (name "unconnected-(JP4-Pad29)") (class "Default")
      (node (ref "JP4") (pin "29") (pinfunction "29_29") (pintype "passive"))
    )
    (net (code "129") (name "unconnected-(JP4-Pad30)") (class "Default")
      (node (ref "JP4") (pin "30") (pinfunction "30_30") (pintype "passive"))
    )
    (net (code "130") (name "unconnected-(JP4-Pad31)") (class "Default")
      (node (ref "JP4") (pin "31") (pinfunction "31_31") (pintype "passive"))
    )
    (net (code "131") (name "unconnected-(JP4-Pad32)") (class "Default")
      (node (ref "JP4") (pin "32") (pinfunction "32_32") (pintype "passive"))
    )
    (net (code "132") (name "unconnected-(SV1-Pad8)") (class "Default")
      (node (ref "SV1") (pin "8") (pinfunction "8_8") (pintype "passive"))
    )
    (net (code "133") (name "unconnected-(SV1-Pad10)") (class "Default")
      (node (ref "SV1") (pin "10") (pinfunction "10_10") (pintype "passive"))
    )
    (net (code "134") (name "unconnected-(SV1-Pad12)") (class "Default")
      (node (ref "SV1") (pin "12") (pinfunction "12_12") (pintype "passive"))
    )
    (net (code "135") (name "unconnected-(SV1-Pad14)") (class "Default")
      (node (ref "SV1") (pin "14") (pinfunction "14_14") (pintype "passive"))
    )
    (net (code "136") (name "unconnected-(SV1-Pad16)") (class "Default")
      (node (ref "SV1") (pin "16") (pinfunction "16_16") (pintype "passive"))
    )
    (net (code "137") (name "unconnected-(SV1-Pad19)") (class "Default")
      (node (ref "SV1") (pin "19") (pinfunction "19_19") (pintype "passive"))
    )
    (net (code "138") (name "unconnected-(SV1-Pad20)") (class "Default")
      (node (ref "SV1") (pin "20") (pinfunction "20_20") (pintype "passive"))
    )
  )
)
